# signal_board.net
KiCad netlist of a schematic drawn in EAGLE
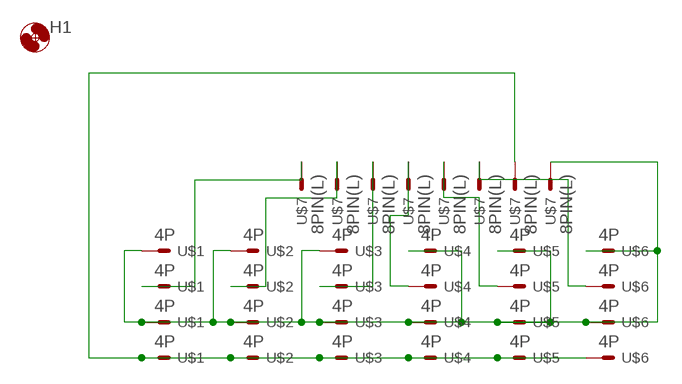
[diagram p0: schematic, sheet 1]

(export (version "E")
  (design (tool "Eeschema 10.0.6"))
  (components
    (comp (ref "H1")
      (value "HOLE3.3M3BOLT")
      (footprint "eagle-import:HOLE3.3")
      (libsource (lib "eagle-import") (part "HOLE3.3M3BOLT"))
    )
    (comp (ref "U$1") (value "4P") (footprint "eagle-import:4P") (libsource (lib "eagle-import") (part "4P")))
    (comp (ref "U$2") (value "4P") (footprint "eagle-import:4P") (libsource (lib "eagle-import") (part "4P")))
    (comp (ref "U$3") (value "4P") (footprint "eagle-import:4P") (libsource (lib "eagle-import") (part "4P")))
    (comp (ref "U$4") (value "4P") (footprint "eagle-import:4P") (libsource (lib "eagle-import") (part "4P")))
    (comp (ref "U$5") (value "4P") (footprint "eagle-import:4P") (libsource (lib "eagle-import") (part "4P")))
    (comp (ref "U$6") (value "4P") (footprint "eagle-import:4P") (libsource (lib "eagle-import") (part "4P")))
    (comp (ref "U$7")
      (value "8PIN(L)")
      (footprint "eagle-import:8PL")
      (libsource (lib "eagle-import") (part "8PIN(L)"))
    )
  )
  (nets
    (net (code "1") (name "Net-(U$1-PadP1)") (class "Default")
      (node (ref "U$1") (pin "P1") (pinfunction "P1_P1") (pintype "passive"))
      (node (ref "U$2") (pin "P1") (pinfunction "P1_P1") (pintype "passive"))
      (node (ref "U$3") (pin "P1") (pinfunction "P1_P1") (pintype "passive"))
      (node (ref "U$4") (pin "P1") (pinfunction "P1_P1") (pintype "passive"))
      (node (ref "U$5") (pin "P1") (pinfunction "P1_P1") (pintype "passive"))
      (node (ref "U$6") (pin "P1") (pinfunction "P1_P1") (pintype "passive"))
      (node (ref "U$7") (pin "P7") (pinfunction "P7_P7") (pintype "passive"))
    )
    (net (code "2") (name "Net-(U$1-PadP2)") (class "Default")
      (node (ref "U$1") (pin "P2") (pinfunction "P2_P2") (pintype "passive"))
      (node (ref "U$1") (pin "P4") (pinfunction "P4_P4") (pintype "passive"))
      (node (ref "U$2") (pin "P2") (pinfunction "P2_P2") (pintype "passive"))
      (node (ref "U$2") (pin "P4") (pinfunction "P4_P4") (pintype "passive"))
      (node (ref "U$3") (pin "P2") (pinfunction "P2_P2") (pintype "passive"))
      (node (ref "U$3") (pin "P4") (pinfunction "P4_P4") (pintype "passive"))
      (node (ref "U$4") (pin "P2") (pinfunction "P2_P2") (pintype "passive"))
      (node (ref "U$4") (pin "P4") (pinfunction "P4_P4") (pintype "passive"))
      (node (ref "U$5") (pin "P2") (pinfunction "P2_P2") (pintype "passive"))
      (node (ref "U$5") (pin "P4") (pinfunction "P4_P4") (pintype "passive"))
      (node (ref "U$6") (pin "P2") (pinfunction "P2_P2") (pintype "passive"))
      (node (ref "U$6") (pin "P4") (pinfunction "P4_P4") (pintype "passive"))
      (node (ref "U$7") (pin "P8") (pinfunction "P8_P8") (pintype "passive"))
    )
    (net (code "3") (name "Net-(U$1-PadP3)") (class "Default")
      (node (ref "U$1") (pin "P3") (pinfunction "P3_P3") (pintype "passive"))
      (node (ref "U$7") (pin "P1") (pinfunction "P1_P1") (pintype "passive"))
    )
    (net (code "4") (name "Net-(U$2-PadP3)") (class "Default")
      (node (ref "U$2") (pin "P3") (pinfunction "P3_P3") (pintype "passive"))
      (node (ref "U$7") (pin "P2") (pinfunction "P2_P2") (pintype "passive"))
    )
    (net (code "5") (name "Net-(U$3-PadP3)") (class "Default")
      (node (ref "U$3") (pin "P3") (pinfunction "P3_P3") (pintype "passive"))
      (node (ref "U$7") (pin "P3") (pinfunction "P3_P3") (pintype "passive"))
    )
    (net (code "6") (name "Net-(U$4-PadP3)") (class "Default")
      (node (ref "U$4") (pin "P3") (pinfunction "P3_P3") (pintype "passive"))
      (node (ref "U$7") (pin "P4") (pinfunction "P4_P4") (pintype "passive"))
    )
    (net (code "7") (name "Net-(U$5-PadP3)") (class "Default")
      (node (ref "U$5") (pin "P3") (pinfunction "P3_P3") (pintype "passive"))
      (node (ref "U$7") (pin "P5") (pinfunction "P5_P5") (pintype "passive"))
    )
    (net (code "8") (name "Net-(U$6-PadP3)") (class "Default")
      (node (ref "U$6") (pin "P3") (pinfunction "P3_P3") (pintype "passive"))
      (node (ref "U$7") (pin "P6") (pinfunction "P6_P6") (pintype "passive"))
    )
  )
)
